# SD_Card.net
KiCad netlist of a schematic drawn in Altium Designer
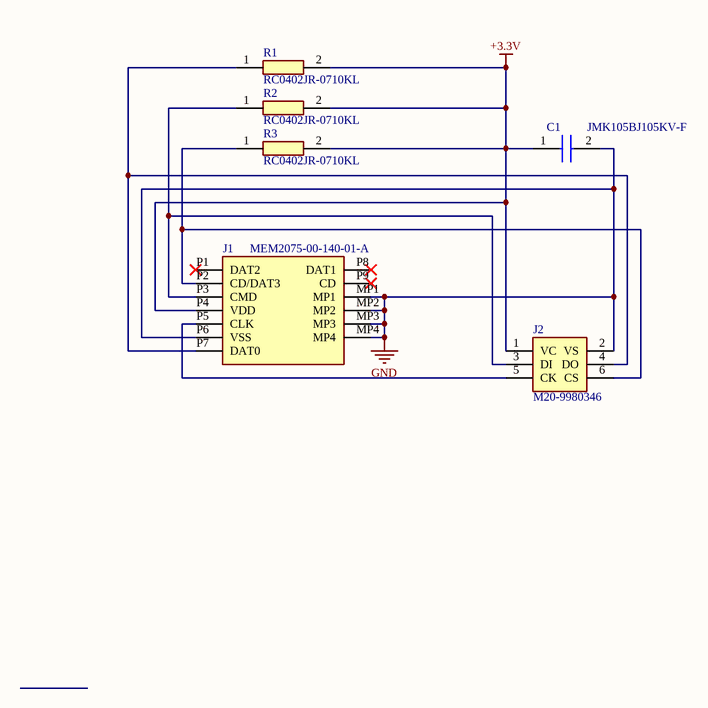
[diagram p0: SD_Card.SchDoc]

(export (version "E")
  (design (tool "Eeschema 10.0.6"))
  (components
    (comp (ref "C1")
      (value "JMK105BJ105KV-F")
      (footprint "SamacSys:CAPC1005X55N")
      (description "Capacitor")
      (fields (field (name "MOUSER PART NUMBER") "963-JMK105BJ105KV-F"))
      (libsource (lib "*") (part "JMK105BJ105KV-F"))
    )
    (comp (ref "J1")
      (value "MEM2075-00-140-01-A")
      (footprint "SamacSys:MEM20750014001A")
      (description "Connector")
      (fields (field (name "MOUSER PART NUMBER") "640-MEM20750014001A"))
      (libsource (lib "*") (part "MEM2075-00-140-01-A"))
    )
    (comp (ref "J2")
      (value "M20-9980346")
      (footprint "SamacSys:HDRV6W64P254_2X3_762X508X868P")
      (description "Connector")
      (fields (field (name "MOUSER PART NUMBER") "855-M20-9980346"))
      (libsource (lib "*") (part "M20-9980346"))
    )
    (comp (ref "R1")
      (value "RC0402JR-0710KL")
      (footprint "SamacSys:RESC1005X40N")
      (description "Resistor")
      (fields (field (name "MOUSER PART NUMBER") "603-RC0402JR-0710KL"))
      (libsource (lib "*") (part "RC0402JR-0710KL"))
    )
    (comp (ref "R2")
      (value "RC0402JR-0710KL")
      (footprint "SamacSys:RESC1005X40N")
      (description "Resistor")
      (fields (field (name "MOUSER PART NUMBER") "603-RC0402JR-0710KL"))
      (libsource (lib "*") (part "RC0402JR-0710KL"))
    )
    (comp (ref "R3")
      (value "RC0402JR-0710KL")
      (footprint "SamacSys:RESC1005X40N")
      (description "Resistor")
      (fields (field (name "MOUSER PART NUMBER") "603-RC0402JR-0710KL"))
      (libsource (lib "*") (part "RC0402JR-0710KL"))
    )
  )
  (nets
    (net (code "1") (name "+3.3V") (class "Default")
      (node (ref "C1") (pin "1") (pinfunction "1_1") (pintype "passive"))
      (node (ref "J1") (pin "P4") (pinfunction "VDD_P4") (pintype "passive"))
      (node (ref "J2") (pin "1") (pinfunction "VC_1") (pintype "passive"))
      (node (ref "R1") (pin "2") (pinfunction "2_2") (pintype "passive"))
      (node (ref "R2") (pin "2") (pinfunction "2_2") (pintype "passive"))
      (node (ref "R3") (pin "2") (pinfunction "2_2") (pintype "passive"))
    )
    (net (code "2") (name "GND") (class "Default")
      (node (ref "C1") (pin "2") (pinfunction "2_2") (pintype "passive"))
      (node (ref "J1") (pin "MP1") (pinfunction "MP1_MP1") (pintype "passive"))
      (node (ref "J1") (pin "MP2") (pinfunction "MP2_MP2") (pintype "passive"))
      (node (ref "J1") (pin "MP3") (pinfunction "MP3_MP3") (pintype "passive"))
      (node (ref "J1") (pin "MP4") (pinfunction "MP4_MP4") (pintype "passive"))
      (node (ref "J1") (pin "P6") (pinfunction "VSS_P6") (pintype "passive"))
      (node (ref "J2") (pin "2") (pinfunction "VS_2") (pintype "passive"))
    )
    (net (code "3") (name "Net-(J1-CD{slash}DAT3)") (class "Default")
      (node (ref "J1") (pin "P2") (pinfunction "CD/DAT3_P2") (pintype "passive"))
      (node (ref "J2") (pin "6") (pinfunction "CS_6") (pintype "passive"))
      (node (ref "R3") (pin "1") (pinfunction "1_1") (pintype "passive"))
    )
    (net (code "4") (name "Net-(J1-CLK)") (class "Default")
      (node (ref "J1") (pin "P5") (pinfunction "CLK_P5") (pintype "passive"))
      (node (ref "J2") (pin "5") (pinfunction "CK_5") (pintype "passive"))
    )
    (net (code "5") (name "Net-(J1-CMD)") (class "Default")
      (node (ref "J1") (pin "P3") (pinfunction "CMD_P3") (pintype "passive"))
      (node (ref "J2") (pin "3") (pinfunction "DI_3") (pintype "passive"))
      (node (ref "R2") (pin "1") (pinfunction "1_1") (pintype "passive"))
    )
    (net (code "6") (name "Net-(J1-DAT0)") (class "Default")
      (node (ref "J1") (pin "P7") (pinfunction "DAT0_P7") (pintype "passive"))
      (node (ref "J2") (pin "4") (pinfunction "DO_4") (pintype "passive"))
      (node (ref "R1") (pin "1") (pinfunction "1_1") (pintype "passive"))
    )
    (net (code "7") (name "unconnected-(J1-CD-PadP9)") (class "Default")
      (node (ref "J1") (pin "P9") (pinfunction "CD_P9") (pintype "passive+no_connect"))
    )
    (net (code "8") (name "unconnected-(J1-DAT1-PadP8)") (class "Default")
      (node (ref "J1") (pin "P8") (pinfunction "DAT1_P8") (pintype "passive+no_connect"))
    )
    (net (code "9") (name "unconnected-(J1-DAT2-PadP1)") (class "Default")
      (node (ref "J1") (pin "P1") (pinfunction "DAT2_P1") (pintype "passive+no_connect"))
    )
  )
)
